# breakout_SX1278_blue.net
KiCad netlist of a schematic drawn in EAGLE
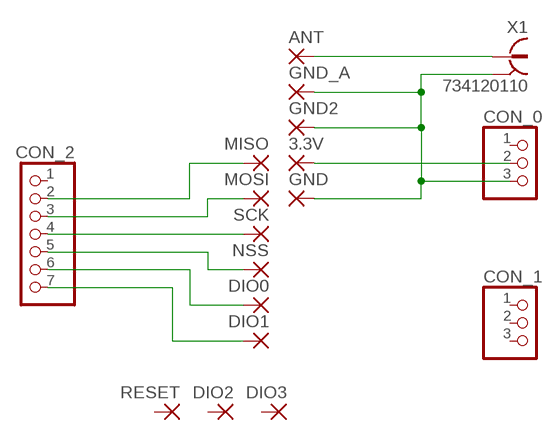
[diagram p0: schematic, sheet 1]

(export (version "E")
  (design (tool "Eeschema 10.0.6"))
  (components
    (comp (ref "3.3V")
      (value "SMD1")
      (footprint "eagle-import:SMD0,65-1,27")
      (libsource (lib "eagle-import") (part "SMD1"))
    )
    (comp (ref "ANT")
      (value "SMD1")
      (footprint "eagle-import:SMD0,65-1,27")
      (libsource (lib "eagle-import") (part "SMD1"))
    )
    (comp (ref "CON_0")
      (value "PINHD-1X3")
      (footprint "eagle-import:1X03")
      (libsource (lib "eagle-import") (part "PINHD-1X3"))
    )
    (comp (ref "CON_1")
      (value "PINHD-1X3")
      (footprint "eagle-import:1X03")
      (libsource (lib "eagle-import") (part "PINHD-1X3"))
    )
    (comp (ref "CON_2")
      (value "PINHD-1X7")
      (footprint "eagle-import:1X07")
      (libsource (lib "eagle-import") (part "PINHD-1X7"))
    )
    (comp (ref "DIO0")
      (value "SMD1")
      (footprint "eagle-import:SMD0,65-1,27")
      (libsource (lib "eagle-import") (part "SMD1"))
    )
    (comp (ref "DIO1")
      (value "SMD1")
      (footprint "eagle-import:SMD0,65-1,27")
      (libsource (lib "eagle-import") (part "SMD1"))
    )
    (comp (ref "DIO2")
      (value "SMD1")
      (footprint "eagle-import:SMD0,65-1,27")
      (libsource (lib "eagle-import") (part "SMD1"))
    )
    (comp (ref "DIO3")
      (value "SMD1")
      (footprint "eagle-import:SMD0,65-1,27")
      (libsource (lib "eagle-import") (part "SMD1"))
    )
    (comp (ref "GND")
      (value "SMD1")
      (footprint "eagle-import:SMD0,65-1,27")
      (libsource (lib "eagle-import") (part "SMD1"))
    )
    (comp (ref "GND2")
      (value "SMD1")
      (footprint "eagle-import:SMD0,65-1,27")
      (libsource (lib "eagle-import") (part "SMD1"))
    )
    (comp (ref "GND_A")
      (value "SMD1")
      (footprint "eagle-import:SMD0,65-1,27")
      (libsource (lib "eagle-import") (part "SMD1"))
    )
    (comp (ref "MISO")
      (value "SMD1")
      (footprint "eagle-import:SMD0,65-1,27")
      (libsource (lib "eagle-import") (part "SMD1"))
    )
    (comp (ref "MOSI")
      (value "SMD1")
      (footprint "eagle-import:SMD0,65-1,27")
      (libsource (lib "eagle-import") (part "SMD1"))
    )
    (comp (ref "NSS")
      (value "SMD1")
      (footprint "eagle-import:SMD0,65-1,27")
      (libsource (lib "eagle-import") (part "SMD1"))
    )
    (comp (ref "RESET")
      (value "SMD1")
      (footprint "eagle-import:SMD0,65-1,27")
      (libsource (lib "eagle-import") (part "SMD1"))
    )
    (comp (ref "SCK")
      (value "SMD1")
      (footprint "eagle-import:SMD0,65-1,27")
      (libsource (lib "eagle-import") (part "SMD1"))
    )
    (comp (ref "X1")
      (value "734120110")
      (footprint "eagle-import:734120110")
      (libsource (lib "eagle-import") (part "734120110"))
    )
  )
  (nets
    (net (code "1") (name "Net-(3.3V-P)") (class "Default")
      (node (ref "3.3V") (pin "1") (pinfunction "P_1") (pintype "passive"))
      (node (ref "CON_0") (pin "2") (pinfunction "2_2") (pintype "passive"))
    )
    (net (code "2") (name "Net-(ANT-P)") (class "Default")
      (node (ref "ANT") (pin "1") (pinfunction "P_1") (pintype "passive"))
      (node (ref "X1") (pin "1") (pinfunction "1_1") (pintype "passive"))
    )
    (net (code "3") (name "Net-(DIO0-P)") (class "Default")
      (node (ref "CON_2") (pin "6") (pinfunction "6_6") (pintype "passive"))
      (node (ref "DIO0") (pin "1") (pinfunction "P_1") (pintype "passive"))
    )
    (net (code "4") (name "Net-(DIO1-P)") (class "Default")
      (node (ref "CON_2") (pin "7") (pinfunction "7_7") (pintype "passive"))
      (node (ref "DIO1") (pin "1") (pinfunction "P_1") (pintype "passive"))
    )
    (net (code "5") (name "Net-(GND-P)") (class "Default")
      (node (ref "CON_0") (pin "3") (pinfunction "3_3") (pintype "passive"))
      (node (ref "GND") (pin "1") (pinfunction "P_1") (pintype "passive"))
      (node (ref "GND2") (pin "1") (pinfunction "P_1") (pintype "passive"))
      (node (ref "GND_A") (pin "1") (pinfunction "P_1") (pintype "passive"))
      (node (ref "X1") (pin "S@1") (pinfunction "2_S@1") (pintype "passive"))
      (node (ref "X1") (pin "S@2") (pinfunction "2_S@2") (pintype "passive"))
      (node (ref "X1") (pin "S@3") (pinfunction "2_S@3") (pintype "passive"))
    )
    (net (code "6") (name "Net-(MISO-P)") (class "Default")
      (node (ref "CON_2") (pin "2") (pinfunction "2_2") (pintype "passive"))
      (node (ref "MISO") (pin "1") (pinfunction "P_1") (pintype "passive"))
    )
    (net (code "7") (name "Net-(MOSI-P)") (class "Default")
      (node (ref "CON_2") (pin "3") (pinfunction "3_3") (pintype "passive"))
      (node (ref "MOSI") (pin "1") (pinfunction "P_1") (pintype "passive"))
    )
    (net (code "8") (name "Net-(NSS-P)") (class "Default")
      (node (ref "CON_2") (pin "5") (pinfunction "5_5") (pintype "passive"))
      (node (ref "NSS") (pin "1") (pinfunction "P_1") (pintype "passive"))
    )
    (net (code "9") (name "Net-(SCK-P)") (class "Default")
      (node (ref "CON_2") (pin "4") (pinfunction "4_4") (pintype "passive"))
      (node (ref "SCK") (pin "1") (pinfunction "P_1") (pintype "passive"))
    )
    (net (code "10") (name "unconnected-(CON_0-Pad1)") (class "Default")
      (node (ref "CON_0") (pin "1") (pinfunction "1_1") (pintype "passive"))
    )
    (net (code "11") (name "unconnected-(CON_1-Pad1)") (class "Default")
      (node (ref "CON_1") (pin "1") (pinfunction "1_1") (pintype "passive"))
    )
    (net (code "12") (name "unconnected-(CON_1-Pad2)") (class "Default")
      (node (ref "CON_1") (pin "2") (pinfunction "2_2") (pintype "passive"))
    )
    (net (code "13") (name "unconnected-(CON_1-Pad3)") (class "Default")
      (node (ref "CON_1") (pin "3") (pinfunction "3_3") (pintype "passive"))
    )
    (net (code "14") (name "unconnected-(CON_2-Pad1)") (class "Default")
      (node (ref "CON_2") (pin "1") (pinfunction "1_1") (pintype "passive"))
    )
    (net (code "15") (name "unconnected-(DIO2-P-Pad1)") (class "Default")
      (node (ref "DIO2") (pin "1") (pinfunction "P_1") (pintype "passive"))
    )
    (net (code "16") (name "unconnected-(DIO3-P-Pad1)") (class "Default")
      (node (ref "DIO3") (pin "1") (pinfunction "P_1") (pintype "passive"))
    )
    (net (code "17") (name "unconnected-(RESET-P-Pad1)") (class "Default")
      (node (ref "RESET") (pin "1") (pinfunction "P_1") (pintype "passive"))
    )
  )
)
